# 13-DSP_PROCESSOR_3-OF-3.net
KiCad netlist of a schematic drawn in Altium Designer
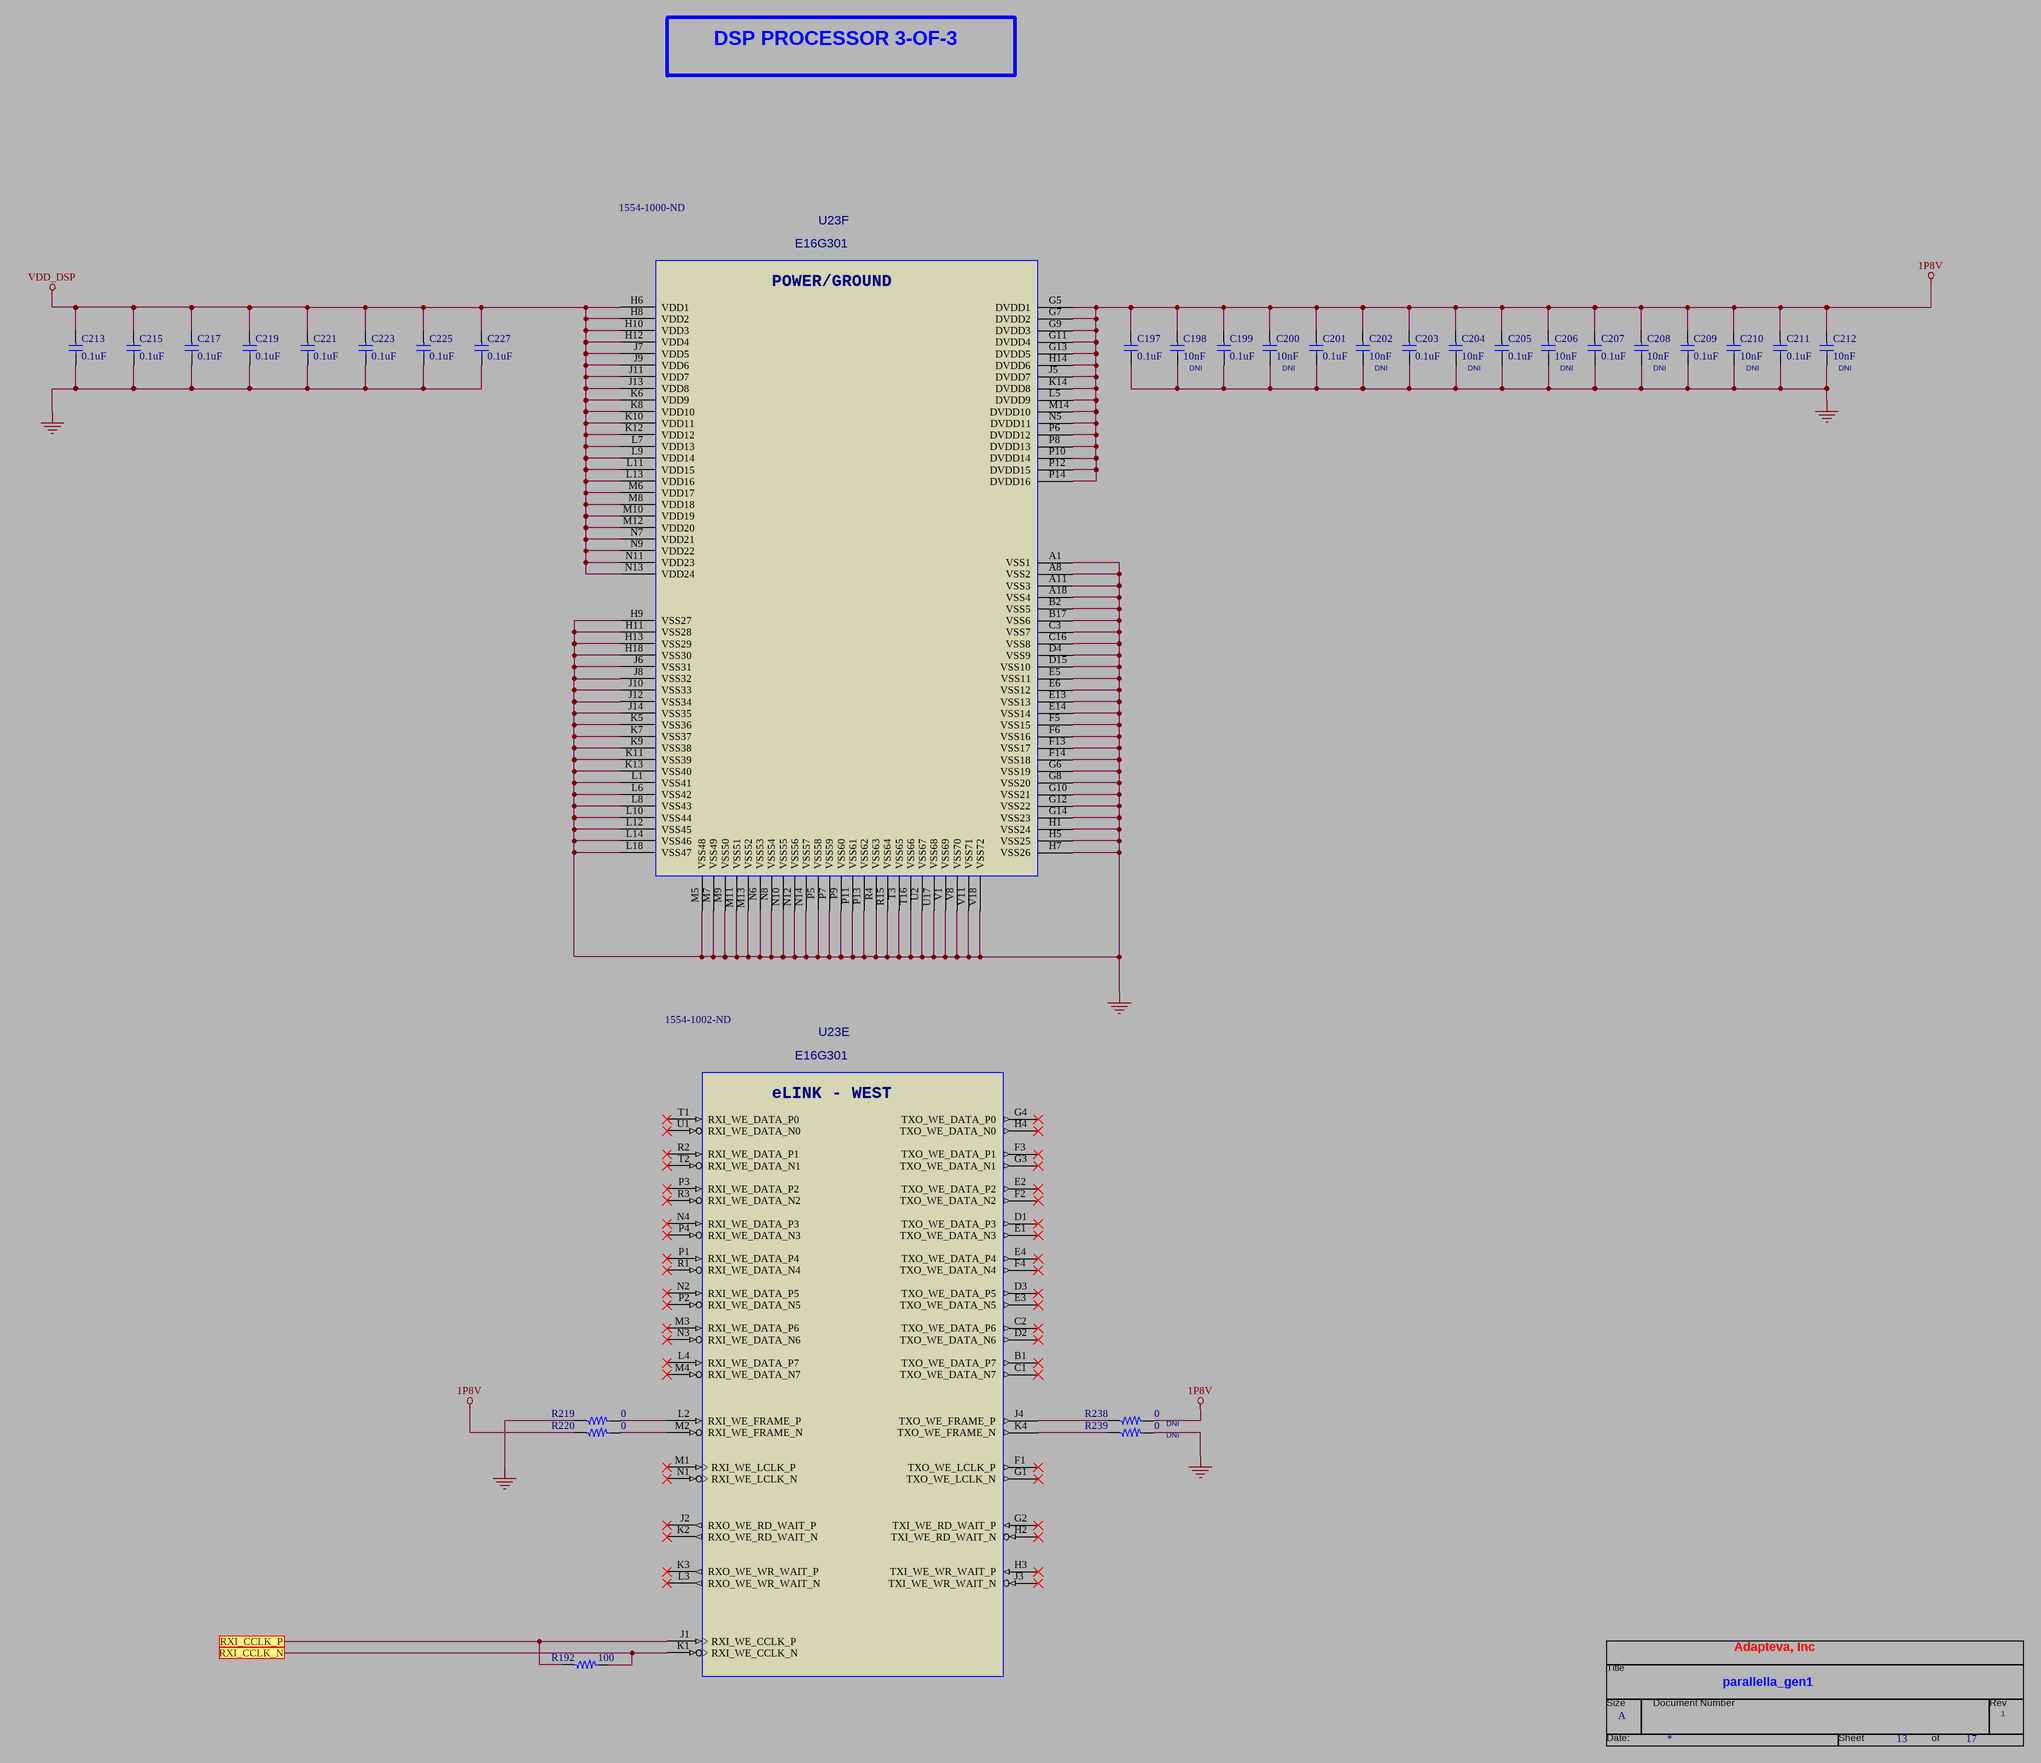
[diagram p0: 13-DSP PROCESSOR 3-OF-3.SchDoc]

(export (version "E")
  (design (tool "Eeschema 10.0.6"))
  (components
    (comp (ref "C197")
      (value "0.1uF")
      (footprint "C0402")
      (description "CAP, 0402, 0.1UF, X5R, 35V")
      (fields (field (name "MFG PART NO") "GMK105BJ104KV-F") (field (name "MFG") "TAIYO YUDEN"))
      (libsource (lib "*") (part "CAP0402_0P1UF_X5R_35V"))
    )
    (comp (ref "C198")
      (value "10nF")
      (footprint "C0402")
      (description "CAP, 0402, 10NF, X7R, 16V")
      (fields
        (field (name "MFG") "TDK")
        (field (name "MFG PART NO") "C1005X7R1C103K")
        (field (name "INSTALL") "DNI")
      )
      (libsource (lib "*") (part "CAP0402_10NF_X7R_16V"))
    )
    (comp (ref "C199")
      (value "0.1uF")
      (footprint "C0402")
      (description "CAP, 0402, 0.1UF, X5R, 35V")
      (fields (field (name "MFG PART NO") "GMK105BJ104KV-F") (field (name "MFG") "TAIYO YUDEN"))
      (libsource (lib "*") (part "CAP0402_0P1UF_X5R_35V"))
    )
    (comp (ref "C200")
      (value "10nF")
      (footprint "C0402")
      (description "CAP, 0402, 10NF, X7R, 16V")
      (fields
        (field (name "MFG") "TDK")
        (field (name "MFG PART NO") "C1005X7R1C103K")
        (field (name "INSTALL") "DNI")
      )
      (libsource (lib "*") (part "CAP0402_10NF_X7R_16V"))
    )
    (comp (ref "C201")
      (value "0.1uF")
      (footprint "C0402")
      (description "CAP, 0402, 0.1UF, X5R, 35V")
      (fields (field (name "MFG PART NO") "GMK105BJ104KV-F") (field (name "MFG") "TAIYO YUDEN"))
      (libsource (lib "*") (part "CAP0402_0P1UF_X5R_35V"))
    )
    (comp (ref "C202")
      (value "10nF")
      (footprint "C0402")
      (description "CAP, 0402, 10NF, X7R, 16V")
      (fields
        (field (name "MFG") "TDK")
        (field (name "MFG PART NO") "C1005X7R1C103K")
        (field (name "INSTALL") "DNI")
      )
      (libsource (lib "*") (part "CAP0402_10NF_X7R_16V"))
    )
    (comp (ref "C203")
      (value "0.1uF")
      (footprint "C0402")
      (description "CAP, 0402, 0.1UF, X5R, 35V")
      (fields (field (name "MFG PART NO") "GMK105BJ104KV-F") (field (name "MFG") "TAIYO YUDEN"))
      (libsource (lib "*") (part "CAP0402_0P1UF_X5R_35V"))
    )
    (comp (ref "C204")
      (value "10nF")
      (footprint "C0402")
      (description "CAP, 0402, 10NF, X7R, 16V")
      (fields
        (field (name "MFG") "TDK")
        (field (name "MFG PART NO") "C1005X7R1C103K")
        (field (name "INSTALL") "DNI")
      )
      (libsource (lib "*") (part "CAP0402_10NF_X7R_16V"))
    )
    (comp (ref "C205")
      (value "0.1uF")
      (footprint "C0402")
      (description "CAP, 0402, 0.1UF, X5R, 35V")
      (fields (field (name "MFG PART NO") "GMK105BJ104KV-F") (field (name "MFG") "TAIYO YUDEN"))
      (libsource (lib "*") (part "CAP0402_0P1UF_X5R_35V"))
    )
    (comp (ref "C206")
      (value "10nF")
      (footprint "C0402")
      (description "CAP, 0402, 10NF, X7R, 16V")
      (fields
        (field (name "MFG") "TDK")
        (field (name "MFG PART NO") "C1005X7R1C103K")
        (field (name "INSTALL") "DNI")
      )
      (libsource (lib "*") (part "CAP0402_10NF_X7R_16V"))
    )
    (comp (ref "C207")
      (value "0.1uF")
      (footprint "C0402")
      (description "CAP, 0402, 0.1UF, X5R, 35V")
      (fields (field (name "MFG PART NO") "GMK105BJ104KV-F") (field (name "MFG") "TAIYO YUDEN"))
      (libsource (lib "*") (part "CAP0402_0P1UF_X5R_35V"))
    )
    (comp (ref "C208")
      (value "10nF")
      (footprint "C0402")
      (description "CAP, 0402, 10NF, X7R, 16V")
      (fields
        (field (name "MFG") "TDK")
        (field (name "MFG PART NO") "C1005X7R1C103K")
        (field (name "INSTALL") "DNI")
      )
      (libsource (lib "*") (part "CAP0402_10NF_X7R_16V"))
    )
    (comp (ref "C209")
      (value "0.1uF")
      (footprint "C0402")
      (description "CAP, 0402, 0.1UF, X5R, 35V")
      (fields (field (name "MFG PART NO") "GMK105BJ104KV-F") (field (name "MFG") "TAIYO YUDEN"))
      (libsource (lib "*") (part "CAP0402_0P1UF_X5R_35V"))
    )
    (comp (ref "C210")
      (value "10nF")
      (footprint "C0402")
      (description "CAP, 0402, 10NF, X7R, 16V")
      (fields
        (field (name "MFG") "TDK")
        (field (name "MFG PART NO") "C1005X7R1C103K")
        (field (name "INSTALL") "DNI")
      )
      (libsource (lib "*") (part "CAP0402_10NF_X7R_16V"))
    )
    (comp (ref "C211")
      (value "0.1uF")
      (footprint "C0402")
      (description "CAP, 0402, 0.1UF, X5R, 35V")
      (fields (field (name "MFG PART NO") "GMK105BJ104KV-F") (field (name "MFG") "TAIYO YUDEN"))
      (libsource (lib "*") (part "CAP0402_0P1UF_X5R_35V"))
    )
    (comp (ref "C212")
      (value "10nF")
      (footprint "C0402")
      (description "CAP, 0402, 10NF, X7R, 16V")
      (fields
        (field (name "MFG") "TDK")
        (field (name "MFG PART NO") "C1005X7R1C103K")
        (field (name "INSTALL") "DNI")
      )
      (libsource (lib "*") (part "CAP0402_10NF_X7R_16V"))
    )
    (comp (ref "C213")
      (value "0.1uF")
      (footprint "C0402")
      (description "CAP, 0402, 0.1UF, X5R, 35V")
      (fields (field (name "MFG PART NO") "GMK105BJ104KV-F") (field (name "MFG") "TAIYO YUDEN"))
      (libsource (lib "*") (part "CAP0402_0P1UF_X5R_35V"))
    )
    (comp (ref "C215")
      (value "0.1uF")
      (footprint "C0402")
      (description "CAP, 0402, 0.1UF, X5R, 35V")
      (fields (field (name "MFG PART NO") "GMK105BJ104KV-F") (field (name "MFG") "TAIYO YUDEN"))
      (libsource (lib "*") (part "CAP0402_0P1UF_X5R_35V"))
    )
    (comp (ref "C217")
      (value "0.1uF")
      (footprint "C0402")
      (description "CAP, 0402, 0.1UF, X5R, 35V")
      (fields (field (name "MFG PART NO") "GMK105BJ104KV-F") (field (name "MFG") "TAIYO YUDEN"))
      (libsource (lib "*") (part "CAP0402_0P1UF_X5R_35V"))
    )
    (comp (ref "C219")
      (value "0.1uF")
      (footprint "C0402")
      (description "CAP, 0402, 0.1UF, X5R, 35V")
      (fields (field (name "MFG PART NO") "GMK105BJ104KV-F") (field (name "MFG") "TAIYO YUDEN"))
      (libsource (lib "*") (part "CAP0402_0P1UF_X5R_35V"))
    )
    (comp (ref "C221")
      (value "0.1uF")
      (footprint "C0402")
      (description "CAP, 0402, 0.1UF, X5R, 35V")
      (fields (field (name "MFG PART NO") "GMK105BJ104KV-F") (field (name "MFG") "TAIYO YUDEN"))
      (libsource (lib "*") (part "CAP0402_0P1UF_X5R_35V"))
    )
    (comp (ref "C223")
      (value "0.1uF")
      (footprint "C0402")
      (description "CAP, 0402, 0.1UF, X5R, 35V")
      (fields (field (name "MFG PART NO") "GMK105BJ104KV-F") (field (name "MFG") "TAIYO YUDEN"))
      (libsource (lib "*") (part "CAP0402_0P1UF_X5R_35V"))
    )
    (comp (ref "C225")
      (value "0.1uF")
      (footprint "C0402")
      (description "CAP, 0402, 0.1UF, X5R, 35V")
      (fields (field (name "MFG PART NO") "GMK105BJ104KV-F") (field (name "MFG") "TAIYO YUDEN"))
      (libsource (lib "*") (part "CAP0402_0P1UF_X5R_35V"))
    )
    (comp (ref "C227")
      (value "0.1uF")
      (footprint "C0402")
      (description "CAP, 0402, 0.1UF, X5R, 35V")
      (fields (field (name "MFG PART NO") "GMK105BJ104KV-F") (field (name "MFG") "TAIYO YUDEN"))
      (libsource (lib "*") (part "CAP0402_0P1UF_X5R_35V"))
    )
    (comp (ref "R192")
      (value "100")
      (footprint "R0402")
      (description "RES, 0402, 100, 1%")
      (fields (field (name "MFG PART NO") "CRCW0402100RFKED") (field (name "MFG") "VISHAY"))
      (libsource (lib "*") (part "RES0402_100"))
    )
    (comp (ref "R219")
      (value "0")
      (footprint "R0402")
      (description "RES, 0402, 0 OHM, 1%")
      (fields (field (name "MFG") "VISHAY") (field (name "MFG PART NO") "CRCW04020000Z0ED"))
      (libsource (lib "*") (part "RES0402_0"))
    )
    (comp (ref "R220")
      (value "0")
      (footprint "R0402")
      (description "RES, 0402, 0 OHM, 1%")
      (fields (field (name "MFG") "VISHAY") (field (name "MFG PART NO") "CRCW04020000Z0ED"))
      (libsource (lib "*") (part "RES0402_0"))
    )
    (comp (ref "R238")
      (value "0")
      (footprint "R0402")
      (description "RES, 0402, 0 OHM, 1%")
      (fields
        (field (name "MFG") "VISHAY")
        (field (name "MFG PART NO") "CRCW04020000Z0ED")
        (field (name "INSTALL") "DNI")
      )
      (libsource (lib "*") (part "RES0402_0"))
    )
    (comp (ref "R239")
      (value "0")
      (footprint "R0402")
      (description "RES, 0402, 0 OHM, 1%")
      (fields
        (field (name "MFG") "VISHAY")
        (field (name "MFG PART NO") "CRCW04020000Z0ED")
        (field (name "INSTALL") "DNI")
      )
      (libsource (lib "*") (part "RES0402_0"))
    )
    (comp (ref "U23")
      (value "16-CORE MICROPROCESSOR")
      (footprint "BGA324_15SQX1P5_P8MMP")
      (description "IC, 16-CORE MICROPROCESSOR, ADAPTEVA, E16G301, BGA324")
      (fields (field (name "VENDOR PN") "E16G301") (field (name "SUPPLIER PART NUMBER 1") "1554-1002-ND"))
      (libsource (lib "*") (part "EPIPHANY_E16G301"))
    )
  )
  (nets
    (net (code "1") (name "/RXI_CCLK_N") (class "Default")
      (node (ref "R192") (pin "2") (pinfunction "2_2") (pintype "passive"))
      (node (ref "U23") (pin "K1") (pinfunction "RXI_WE_CCLK_N_K1") (pintype "input"))
    )
    (net (code "2") (name "/RXI_CCLK_P") (class "Default")
      (node (ref "R192") (pin "1") (pinfunction "1_1") (pintype "passive"))
      (node (ref "U23") (pin "J1") (pinfunction "RXI_WE_CCLK_P_J1") (pintype "input"))
    )
    (net (code "3") (name "1P8V") (class "Default")
      (node (ref "C197") (pin "1") (pinfunction "1_1") (pintype "passive"))
      (node (ref "C198") (pin "1") (pinfunction "1_1") (pintype "passive"))
      (node (ref "C199") (pin "1") (pinfunction "1_1") (pintype "passive"))
      (node (ref "C200") (pin "1") (pinfunction "1_1") (pintype "passive"))
      (node (ref "C201") (pin "1") (pinfunction "1_1") (pintype "passive"))
      (node (ref "C202") (pin "1") (pinfunction "1_1") (pintype "passive"))
      (node (ref "C203") (pin "1") (pinfunction "1_1") (pintype "passive"))
      (node (ref "C204") (pin "1") (pinfunction "1_1") (pintype "passive"))
      (node (ref "C205") (pin "1") (pinfunction "1_1") (pintype "passive"))
      (node (ref "C206") (pin "1") (pinfunction "1_1") (pintype "passive"))
      (node (ref "C207") (pin "1") (pinfunction "1_1") (pintype "passive"))
      (node (ref "C208") (pin "1") (pinfunction "1_1") (pintype "passive"))
      (node (ref "C209") (pin "1") (pinfunction "1_1") (pintype "passive"))
      (node (ref "C210") (pin "1") (pinfunction "1_1") (pintype "passive"))
      (node (ref "C211") (pin "1") (pinfunction "1_1") (pintype "passive"))
      (node (ref "C212") (pin "1") (pinfunction "1_1") (pintype "passive"))
      (node (ref "R220") (pin "1") (pinfunction "1_1") (pintype "passive"))
      (node (ref "R238") (pin "2") (pinfunction "2_2") (pintype "passive"))
      (node (ref "U23") (pin "G11") (pinfunction "DVDD4_G11") (pintype "power_in"))
      (node (ref "U23") (pin "G13") (pinfunction "DVDD5_G13") (pintype "power_in"))
      (node (ref "U23") (pin "G5") (pinfunction "DVDD1_G5") (pintype "power_in"))
      (node (ref "U23") (pin "G7") (pinfunction "DVDD2_G7") (pintype "power_in"))
      (node (ref "U23") (pin "G9") (pinfunction "DVDD3_G9") (pintype "power_in"))
      (node (ref "U23") (pin "H14") (pinfunction "DVDD6_H14") (pintype "power_in"))
      (node (ref "U23") (pin "J5") (pinfunction "DVDD7_J5") (pintype "power_in"))
      (node (ref "U23") (pin "K14") (pinfunction "DVDD8_K14") (pintype "power_in"))
      (node (ref "U23") (pin "L5") (pinfunction "DVDD9_L5") (pintype "power_in"))
      (node (ref "U23") (pin "M14") (pinfunction "DVDD10_M14") (pintype "power_in"))
      (node (ref "U23") (pin "N5") (pinfunction "DVDD11_N5") (pintype "power_in"))
      (node (ref "U23") (pin "P10") (pinfunction "DVDD14_P10") (pintype "power_in"))
      (node (ref "U23") (pin "P12") (pinfunction "DVDD15_P12") (pintype "power_in"))
      (node (ref "U23") (pin "P14") (pinfunction "DVDD16_P14") (pintype "power_in"))
      (node (ref "U23") (pin "P6") (pinfunction "DVDD12_P6") (pintype "power_in"))
      (node (ref "U23") (pin "P8") (pinfunction "DVDD13_P8") (pintype "power_in"))
    )
    (net (code "4") (name "GND") (class "Default")
      (node (ref "C197") (pin "2") (pinfunction "2_2") (pintype "passive"))
      (node (ref "C198") (pin "2") (pinfunction "2_2") (pintype "passive"))
      (node (ref "C199") (pin "2") (pinfunction "2_2") (pintype "passive"))
      (node (ref "C200") (pin "2") (pinfunction "2_2") (pintype "passive"))
      (node (ref "C201") (pin "2") (pinfunction "2_2") (pintype "passive"))
      (node (ref "C202") (pin "2") (pinfunction "2_2") (pintype "passive"))
      (node (ref "C203") (pin "2") (pinfunction "2_2") (pintype "passive"))
      (node (ref "C204") (pin "2") (pinfunction "2_2") (pintype "passive"))
      (node (ref "C205") (pin "2") (pinfunction "2_2") (pintype "passive"))
      (node (ref "C206") (pin "2") (pinfunction "2_2") (pintype "passive"))
      (node (ref "C207") (pin "2") (pinfunction "2_2") (pintype "passive"))
      (node (ref "C208") (pin "2") (pinfunction "2_2") (pintype "passive"))
      (node (ref "C209") (pin "2") (pinfunction "2_2") (pintype "passive"))
      (node (ref "C210") (pin "2") (pinfunction "2_2") (pintype "passive"))
      (node (ref "C211") (pin "2") (pinfunction "2_2") (pintype "passive"))
      (node (ref "C212") (pin "2") (pinfunction "2_2") (pintype "passive"))
      (node (ref "C213") (pin "2") (pinfunction "2_2") (pintype "passive"))
      (node (ref "C215") (pin "2") (pinfunction "2_2") (pintype "passive"))
      (node (ref "C217") (pin "2") (pinfunction "2_2") (pintype "passive"))
      (node (ref "C219") (pin "2") (pinfunction "2_2") (pintype "passive"))
      (node (ref "C221") (pin "2") (pinfunction "2_2") (pintype "passive"))
      (node (ref "C223") (pin "2") (pinfunction "2_2") (pintype "passive"))
      (node (ref "C225") (pin "2") (pinfunction "2_2") (pintype "passive"))
      (node (ref "C227") (pin "2") (pinfunction "2_2") (pintype "passive"))
      (node (ref "R219") (pin "1") (pinfunction "1_1") (pintype "passive"))
      (node (ref "R239") (pin "2") (pinfunction "2_2") (pintype "passive"))
      (node (ref "U23") (pin "A1") (pinfunction "VSS1_A1") (pintype "power_in"))
      (node (ref "U23") (pin "A11") (pinfunction "VSS3_A11") (pintype "power_in"))
      (node (ref "U23") (pin "A18") (pinfunction "VSS4_A18") (pintype "power_in"))
      (node (ref "U23") (pin "A8") (pinfunction "VSS2_A8") (pintype "power_in"))
      (node (ref "U23") (pin "B17") (pinfunction "VSS6_B17") (pintype "power_in"))
      (node (ref "U23") (pin "B2") (pinfunction "VSS5_B2") (pintype "power_in"))
      (node (ref "U23") (pin "C16") (pinfunction "VSS8_C16") (pintype "power_in"))
      (node (ref "U23") (pin "C3") (pinfunction "VSS7_C3") (pintype "power_in"))
      (node (ref "U23") (pin "D15") (pinfunction "VSS10_D15") (pintype "power_in"))
      (node (ref "U23") (pin "D4") (pinfunction "VSS9_D4") (pintype "power_in"))
      (node (ref "U23") (pin "E13") (pinfunction "VSS13_E13") (pintype "power_in"))
      (node (ref "U23") (pin "E14") (pinfunction "VSS14_E14") (pintype "power_in"))
      (node (ref "U23") (pin "E5") (pinfunction "VSS11_E5") (pintype "power_in"))
      (node (ref "U23") (pin "E6") (pinfunction "VSS12_E6") (pintype "power_in"))
      (node (ref "U23") (pin "F13") (pinfunction "VSS17_F13") (pintype "power_in"))
      (node (ref "U23") (pin "F14") (pinfunction "VSS18_F14") (pintype "power_in"))
      (node (ref "U23") (pin "F5") (pinfunction "VSS15_F5") (pintype "power_in"))
      (node (ref "U23") (pin "F6") (pinfunction "VSS16_F6") (pintype "power_in"))
      (node (ref "U23") (pin "G10") (pinfunction "VSS21_G10") (pintype "power_in"))
      (node (ref "U23") (pin "G12") (pinfunction "VSS22_G12") (pintype "power_in"))
      (node (ref "U23") (pin "G14") (pinfunction "VSS23_G14") (pintype "power_in"))
      (node (ref "U23") (pin "G6") (pinfunction "VSS19_G6") (pintype "power_in"))
      (node (ref "U23") (pin "G8") (pinfunction "VSS20_G8") (pintype "power_in"))
      (node (ref "U23") (pin "H1") (pinfunction "VSS24_H1") (pintype "power_in"))
      (node (ref "U23") (pin "H11") (pinfunction "VSS28_H11") (pintype "power_in"))
      (node (ref "U23") (pin "H13") (pinfunction "VSS29_H13") (pintype "power_in"))
      (node (ref "U23") (pin "H18") (pinfunction "VSS30_H18") (pintype "power_in"))
      (node (ref "U23") (pin "H5") (pinfunction "VSS25_H5") (pintype "power_in"))
      (node (ref "U23") (pin "H7") (pinfunction "VSS26_H7") (pintype "power_in"))
      (node (ref "U23") (pin "H9") (pinfunction "VSS27_H9") (pintype "power_in"))
      (node (ref "U23") (pin "J10") (pinfunction "VSS33_J10") (pintype "power_in"))
      (node (ref "U23") (pin "J12") (pinfunction "VSS34_J12") (pintype "power_in"))
      (node (ref "U23") (pin "J14") (pinfunction "VSS35_J14") (pintype "power_in"))
      (node (ref "U23") (pin "J6") (pinfunction "VSS31_J6") (pintype "power_in"))
      (node (ref "U23") (pin "J8") (pinfunction "VSS32_J8") (pintype "power_in"))
      (node (ref "U23") (pin "K11") (pinfunction "VSS39_K11") (pintype "power_in"))
      (node (ref "U23") (pin "K13") (pinfunction "VSS40_K13") (pintype "power_in"))
      (node (ref "U23") (pin "K5") (pinfunction "VSS36_K5") (pintype "power_in"))
      (node (ref "U23") (pin "K7") (pinfunction "VSS37_K7") (pintype "power_in"))
      (node (ref "U23") (pin "K9") (pinfunction "VSS38_K9") (pintype "power_in"))
      (node (ref "U23") (pin "L1") (pinfunction "VSS41_L1") (pintype "power_in"))
      (node (ref "U23") (pin "L10") (pinfunction "VSS44_L10") (pintype "power_in"))
      (node (ref "U23") (pin "L12") (pinfunction "VSS45_L12") (pintype "power_in"))
      (node (ref "U23") (pin "L14") (pinfunction "VSS46_L14") (pintype "power_in"))
      (node (ref "U23") (pin "L18") (pinfunction "VSS47_L18") (pintype "power_in"))
      (node (ref "U23") (pin "L6") (pinfunction "VSS42_L6") (pintype "power_in"))
      (node (ref "U23") (pin "L8") (pinfunction "VSS43_L8") (pintype "power_in"))
      (node (ref "U23") (pin "M11") (pinfunction "VSS51_M11") (pintype "power_in"))
      (node (ref "U23") (pin "M13") (pinfunction "VSS52_M13") (pintype "power_in"))
      (node (ref "U23") (pin "M5") (pinfunction "VSS48_M5") (pintype "power_in"))
      (node (ref "U23") (pin "M7") (pinfunction "VSS49_M7") (pintype "power_in"))
      (node (ref "U23") (pin "M9") (pinfunction "VSS50_M9") (pintype "power_in"))
      (node (ref "U23") (pin "N10") (pinfunction "VSS55_N10") (pintype "power_in"))
      (node (ref "U23") (pin "N12") (pinfunction "VSS56_N12") (pintype "power_in"))
      (node (ref "U23") (pin "N14") (pinfunction "VSS57_N14") (pintype "power_in"))
      (node (ref "U23") (pin "N6") (pinfunction "VSS53_N6") (pintype "power_in"))
      (node (ref "U23") (pin "N8") (pinfunction "VSS54_N8") (pintype "power_in"))
      (node (ref "U23") (pin "P11") (pinfunction "VSS61_P11") (pintype "power_in"))
      (node (ref "U23") (pin "P13") (pinfunction "VSS62_P13") (pintype "power_in"))
      (node (ref "U23") (pin "P5") (pinfunction "VSS58_P5") (pintype "power_in"))
      (node (ref "U23") (pin "P7") (pinfunction "VSS59_P7") (pintype "power_in"))
      (node (ref "U23") (pin "P9") (pinfunction "VSS60_P9") (pintype "power_in"))
      (node (ref "U23") (pin "R15") (pinfunction "VSS64_R15") (pintype "power_in"))
      (node (ref "U23") (pin "R4") (pinfunction "VSS63_R4") (pintype "power_in"))
      (node (ref "U23") (pin "T16") (pinfunction "VSS66_T16") (pintype "power_in"))
      (node (ref "U23") (pin "T3") (pinfunction "VSS65_T3") (pintype "power_in"))
      (node (ref "U23") (pin "U17") (pinfunction "VSS68_U17") (pintype "power_in"))
      (node (ref "U23") (pin "U2") (pinfunction "VSS67_U2") (pintype "power_in"))
      (node (ref "U23") (pin "V1") (pinfunction "VSS69_V1") (pintype "power_in"))
      (node (ref "U23") (pin "V11") (pinfunction "VSS71_V11") (pintype "power_in"))
      (node (ref "U23") (pin "V18") (pinfunction "VSS72_V18") (pintype "power_in"))
      (node (ref "U23") (pin "V8") (pinfunction "VSS70_V8") (pintype "power_in"))
    )
    (net (code "5") (name "Net-(U23E-RXI_WE_FRAME_N)") (class "Default")
      (node (ref "R220") (pin "2") (pinfunction "2_2") (pintype "passive"))
      (node (ref "U23") (pin "M2") (pinfunction "RXI_WE_FRAME_N_M2") (pintype "input"))
    )
    (net (code "6") (name "Net-(U23E-RXI_WE_FRAME_P)") (class "Default")
      (node (ref "R219") (pin "2") (pinfunction "2_2") (pintype "passive"))
      (node (ref "U23") (pin "L2") (pinfunction "RXI_WE_FRAME_P_L2") (pintype "input"))
    )
    (net (code "7") (name "Net-(U23E-TXO_WE_FRAME_N)") (class "Default")
      (node (ref "R239") (pin "1") (pinfunction "1_1") (pintype "passive"))
      (node (ref "U23") (pin "K4") (pinfunction "TXO_WE_FRAME_N_K4") (pintype "output"))
    )
    (net (code "8") (name "Net-(U23E-TXO_WE_FRAME_P)") (class "Default")
      (node (ref "R238") (pin "1") (pinfunction "1_1") (pintype "passive"))
      (node (ref "U23") (pin "J4") (pinfunction "TXO_WE_FRAME_P_J4") (pintype "output"))
    )
    (net (code "9") (name "VDD_DSP") (class "Default")
      (node (ref "C213") (pin "1") (pinfunction "1_1") (pintype "passive"))
      (node (ref "C215") (pin "1") (pinfunction "1_1") (pintype "passive"))
      (node (ref "C217") (pin "1") (pinfunction "1_1") (pintype "passive"))
      (node (ref "C219") (pin "1") (pinfunction "1_1") (pintype "passive"))
      (node (ref "C221") (pin "1") (pinfunction "1_1") (pintype "passive"))
      (node (ref "C223") (pin "1") (pinfunction "1_1") (pintype "passive"))
      (node (ref "C225") (pin "1") (pinfunction "1_1") (pintype "passive"))
      (node (ref "C227") (pin "1") (pinfunction "1_1") (pintype "passive"))
      (node (ref "U23") (pin "H10") (pinfunction "VDD3_H10") (pintype "power_in"))
      (node (ref "U23") (pin "H12") (pinfunction "VDD4_H12") (pintype "power_in"))
      (node (ref "U23") (pin "H6") (pinfunction "VDD1_H6") (pintype "power_in"))
      (node (ref "U23") (pin "H8") (pinfunction "VDD2_H8") (pintype "power_in"))
      (node (ref "U23") (pin "J11") (pinfunction "VDD7_J11") (pintype "power_in"))
      (node (ref "U23") (pin "J13") (pinfunction "VDD8_J13") (pintype "power_in"))
      (node (ref "U23") (pin "J7") (pinfunction "VDD5_J7") (pintype "power_in"))
      (node (ref "U23") (pin "J9") (pinfunction "VDD6_J9") (pintype "power_in"))
      (node (ref "U23") (pin "K10") (pinfunction "VDD11_K10") (pintype "power_in"))
      (node (ref "U23") (pin "K12") (pinfunction "VDD12_K12") (pintype "power_in"))
      (node (ref "U23") (pin "K6") (pinfunction "VDD9_K6") (pintype "power_in"))
      (node (ref "U23") (pin "K8") (pinfunction "VDD10_K8") (pintype "power_in"))
      (node (ref "U23") (pin "L11") (pinfunction "VDD15_L11") (pintype "power_in"))
      (node (ref "U23") (pin "L13") (pinfunction "VDD16_L13") (pintype "power_in"))
      (node (ref "U23") (pin "L7") (pinfunction "VDD13_L7") (pintype "power_in"))
      (node (ref "U23") (pin "L9") (pinfunction "VDD14_L9") (pintype "power_in"))
      (node (ref "U23") (pin "M10") (pinfunction "VDD19_M10") (pintype "power_in"))
      (node (ref "U23") (pin "M12") (pinfunction "VDD20_M12") (pintype "power_in"))
      (node (ref "U23") (pin "M6") (pinfunction "VDD17_M6") (pintype "power_in"))
      (node (ref "U23") (pin "M8") (pinfunction "VDD18_M8") (pintype "power_in"))
      (node (ref "U23") (pin "N11") (pinfunction "VDD23_N11") (pintype "power_in"))
      (node (ref "U23") (pin "N13") (pinfunction "VDD24_N13") (pintype "power_in"))
      (node (ref "U23") (pin "N7") (pinfunction "VDD21_N7") (pintype "power_in"))
      (node (ref "U23") (pin "N9") (pinfunction "VDD22_N9") (pintype "power_in"))
    )
    (net (code "10") (name "unconnected-(U23E-RXI_WE_DATA_N0-PadU1)") (class "Default")
      (node (ref "U23") (pin "U1") (pinfunction "RXI_WE_DATA_N0_U1") (pintype "input+no_connect"))
    )
    (net (code "11") (name "unconnected-(U23E-RXI_WE_DATA_N1-PadT2)") (class "Default")
      (node (ref "U23") (pin "T2") (pinfunction "RXI_WE_DATA_N1_T2") (pintype "input+no_connect"))
    )
    (net (code "12") (name "unconnected-(U23E-RXI_WE_DATA_N2-PadR3)") (class "Default")
      (node (ref "U23") (pin "R3") (pinfunction "RXI_WE_DATA_N2_R3") (pintype "input+no_connect"))
    )
    (net (code "13") (name "unconnected-(U23E-RXI_WE_DATA_N3-PadP4)") (class "Default")
      (node (ref "U23") (pin "P4") (pinfunction "RXI_WE_DATA_N3_P4") (pintype "input+no_connect"))
    )
    (net (code "14") (name "unconnected-(U23E-RXI_WE_DATA_N4-PadR1)") (class "Default")
      (node (ref "U23") (pin "R1") (pinfunction "RXI_WE_DATA_N4_R1") (pintype "input+no_connect"))
    )
    (net (code "15") (name "unconnected-(U23E-RXI_WE_DATA_N5-PadP2)") (class "Default")
      (node (ref "U23") (pin "P2") (pinfunction "RXI_WE_DATA_N5_P2") (pintype "input+no_connect"))
    )
    (net (code "16") (name "unconnected-(U23E-RXI_WE_DATA_N6-PadN3)") (class "Default")
      (node (ref "U23") (pin "N3") (pinfunction "RXI_WE_DATA_N6_N3") (pintype "input+no_connect"))
    )
    (net (code "17") (name "unconnected-(U23E-RXI_WE_DATA_N7-PadM4)") (class "Default")
      (node (ref "U23") (pin "M4") (pinfunction "RXI_WE_DATA_N7_M4") (pintype "input+no_connect"))
    )
    (net (code "18") (name "unconnected-(U23E-RXI_WE_DATA_P0-PadT1)") (class "Default")
      (node (ref "U23") (pin "T1") (pinfunction "RXI_WE_DATA_P0_T1") (pintype "input+no_connect"))
    )
    (net (code "19") (name "unconnected-(U23E-RXI_WE_DATA_P1-PadR2)") (class "Default")
      (node (ref "U23") (pin "R2") (pinfunction "RXI_WE_DATA_P1_R2") (pintype "input+no_connect"))
    )
    (net (code "20") (name "unconnected-(U23E-RXI_WE_DATA_P2-PadP3)") (class "Default")
      (node (ref "U23") (pin "P3") (pinfunction "RXI_WE_DATA_P2_P3") (pintype "input+no_connect"))
    )
    (net (code "21") (name "unconnected-(U23E-RXI_WE_DATA_P3-PadN4)") (class "Default")
      (node (ref "U23") (pin "N4") (pinfunction "RXI_WE_DATA_P3_N4") (pintype "input+no_connect"))
    )
    (net (code "22") (name "unconnected-(U23E-RXI_WE_DATA_P4-PadP1)") (class "Default")
      (node (ref "U23") (pin "P1") (pinfunction "RXI_WE_DATA_P4_P1") (pintype "input+no_connect"))
    )
    (net (code "23") (name "unconnected-(U23E-RXI_WE_DATA_P5-PadN2)") (class "Default")
      (node (ref "U23") (pin "N2") (pinfunction "RXI_WE_DATA_P5_N2") (pintype "input+no_connect"))
    )
    (net (code "24") (name "unconnected-(U23E-RXI_WE_DATA_P6-PadM3)") (class "Default")
      (node (ref "U23") (pin "M3") (pinfunction "RXI_WE_DATA_P6_M3") (pintype "input+no_connect"))
    )
    (net (code "25") (name "unconnected-(U23E-RXI_WE_DATA_P7-PadL4)") (class "Default")
      (node (ref "U23") (pin "L4") (pinfunction "RXI_WE_DATA_P7_L4") (pintype "input+no_connect"))
    )
    (net (code "26") (name "unconnected-(U23E-RXI_WE_LCLK_N-PadN1)") (class "Default")
      (node (ref "U23") (pin "N1") (pinfunction "RXI_WE_LCLK_N_N1") (pintype "input+no_connect"))
    )
    (net (code "27") (name "unconnected-(U23E-RXI_WE_LCLK_P-PadM1)") (class "Default")
      (node (ref "U23") (pin "M1") (pinfunction "RXI_WE_LCLK_P_M1") (pintype "input+no_connect"))
    )
    (net (code "28") (name "unconnected-(U23E-RXO_WE_RD_WAIT_N-PadK2)") (class "Default")
      (node (ref "U23") (pin "K2") (pinfunction "RXO_WE_RD_WAIT_N_K2") (pintype "output+no_connect"))
    )
    (net (code "29") (name "unconnected-(U23E-RXO_WE_RD_WAIT_P-PadJ2)") (class "Default")
      (node (ref "U23") (pin "J2") (pinfunction "RXO_WE_RD_WAIT_P_J2") (pintype "output+no_connect"))
    )
    (net (code "30") (name "unconnected-(U23E-RXO_WE_WR_WAIT_N-PadL3)") (class "Default")
      (node (ref "U23") (pin "L3") (pinfunction "RXO_WE_WR_WAIT_N_L3") (pintype "output+no_connect"))
    )
    (net (code "31") (name "unconnected-(U23E-RXO_WE_WR_WAIT_P-PadK3)") (class "Default")
      (node (ref "U23") (pin "K3") (pinfunction "RXO_WE_WR_WAIT_P_K3") (pintype "output+no_connect"))
    )
    (net (code "32") (name "unconnected-(U23E-TXI_WE_RD_WAIT_N-PadH2)") (class "Default")
      (node (ref "U23") (pin "H2") (pinfunction "TXI_WE_RD_WAIT_N_H2") (pintype "input+no_connect"))
    )
    (net (code "33") (name "unconnected-(U23E-TXI_WE_RD_WAIT_P-PadG2)") (class "Default")
      (node (ref "U23") (pin "G2") (pinfunction "TXI_WE_RD_WAIT_P_G2") (pintype "input+no_connect"))
    )
    (net (code "34") (name "unconnected-(U23E-TXI_WE_WR_WAIT_N-PadJ3)") (class "Default")
      (node (ref "U23") (pin "J3") (pinfunction "TXI_WE_WR_WAIT_N_J3") (pintype "input+no_connect"))
    )
    (net (code "35") (name "unconnected-(U23E-TXI_WE_WR_WAIT_P-PadH3)") (class "Default")
      (node (ref "U23") (pin "H3") (pinfunction "TXI_WE_WR_WAIT_P_H3") (pintype "input+no_connect"))
    )
    (net (code "36") (name "unconnected-(U23E-TXO_WE_DATA_N0-PadH4)") (class "Default")
      (node (ref "U23") (pin "H4") (pinfunction "TXO_WE_DATA_N0_H4") (pintype "output+no_connect"))
    )
    (net (code "37") (name "unconnected-(U23E-TXO_WE_DATA_N1-PadG3)") (class "Default")
      (node (ref "U23") (pin "G3") (pinfunction "TXO_WE_DATA_N1_G3") (pintype "output+no_connect"))
    )
    (net (code "38") (name "unconnected-(U23E-TXO_WE_DATA_N2-PadF2)") (class "Default")
      (node (ref "U23") (pin "F2") (pinfunction "TXO_WE_DATA_N2_F2") (pintype "output+no_connect"))
    )
    (net (code "39") (name "unconnected-(U23E-TXO_WE_DATA_N3-PadE1)") (class "Default")
      (node (ref "U23") (pin "E1") (pinfunction "TXO_WE_DATA_N3_E1") (pintype "output+no_connect"))
    )
    (net (code "40") (name "unconnected-(U23E-TXO_WE_DATA_N4-PadF4)") (class "Default")
      (node (ref "U23") (pin "F4") (pinfunction "TXO_WE_DATA_N4_F4") (pintype "output+no_connect"))
    )
    (net (code "41") (name "unconnected-(U23E-TXO_WE_DATA_N5-PadE3)") (class "Default")
      (node (ref "U23") (pin "E3") (pinfunction "TXO_WE_DATA_N5_E3") (pintype "output+no_connect"))
    )
    (net (code "42") (name "unconnected-(U23E-TXO_WE_DATA_N6-PadD2)") (class "Default")
      (node (ref "U23") (pin "D2") (pinfunction "TXO_WE_DATA_N6_D2") (pintype "output+no_connect"))
    )
    (net (code "43") (name "unconnected-(U23E-TXO_WE_DATA_N7-PadC1)") (class "Default")
      (node (ref "U23") (pin "C1") (pinfunction "TXO_WE_DATA_N7_C1") (pintype "output+no_connect"))
    )
    (net (code "44") (name "unconnected-(U23E-TXO_WE_DATA_P0-PadG4)") (class "Default")
      (node (ref "U23") (pin "G4") (pinfunction "TXO_WE_DATA_P0_G4") (pintype "output+no_connect"))
    )
    (net (code "45") (name "unconnected-(U23E-TXO_WE_DATA_P1-PadF3)") (class "Default")
      (node (ref "U23") (pin "F3") (pinfunction "TXO_WE_DATA_P1_F3") (pintype "output+no_connect"))
    )
    (net (code "46") (name "unconnected-(U23E-TXO_WE_DATA_P2-PadE2)") (class "Default")
      (node (ref "U23") (pin "E2") (pinfunction "TXO_WE_DATA_P2_E2") (pintype "output+no_connect"))
    )
    (net (code "47") (name "unconnected-(U23E-TXO_WE_DATA_P3-PadD1)") (class "Default")
      (node (ref "U23") (pin "D1") (pinfunction "TXO_WE_DATA_P3_D1") (pintype "output+no_connect"))
    )
    (net (code "48") (name "unconnected-(U23E-TXO_WE_DATA_P4-PadE4)") (class "Default")
      (node (ref "U23") (pin "E4") (pinfunction "TXO_WE_DATA_P4_E4") (pintype "output+no_connect"))
    )
    (net (code "49") (name "unconnected-(U23E-TXO_WE_DATA_P5-PadD3)") (class "Default")
      (node (ref "U23") (pin "D3") (pinfunction "TXO_WE_DATA_P5_D3") (pintype "output+no_connect"))
    )
    (net (code "50") (name "unconnected-(U23E-TXO_WE_DATA_P6-PadC2)") (class "Default")
      (node (ref "U23") (pin "C2") (pinfunction "TXO_WE_DATA_P6_C2") (pintype "output+no_connect"))
    )
    (net (code "51") (name "unconnected-(U23E-TXO_WE_DATA_P7-PadB1)") (class "Default")
      (node (ref "U23") (pin "B1") (pinfunction "TXO_WE_DATA_P7_B1") (pintype "output+no_connect"))
    )
    (net (code "52") (name "unconnected-(U23E-TXO_WE_LCLK_N-PadG1)") (class "Default")
      (node (ref "U23") (pin "G1") (pinfunction "TXO_WE_LCLK_N_G1") (pintype "output+no_connect"))
    )
    (net (code "53") (name "unconnected-(U23E-TXO_WE_LCLK_P-PadF1)") (class "Default")
      (node (ref "U23") (pin "F1") (pinfunction "TXO_WE_LCLK_P_F1") (pintype "output+no_connect"))
    )
  )
)
